# Proiect_TSC_v38.net
KiCad netlist of a schematic drawn in EAGLE
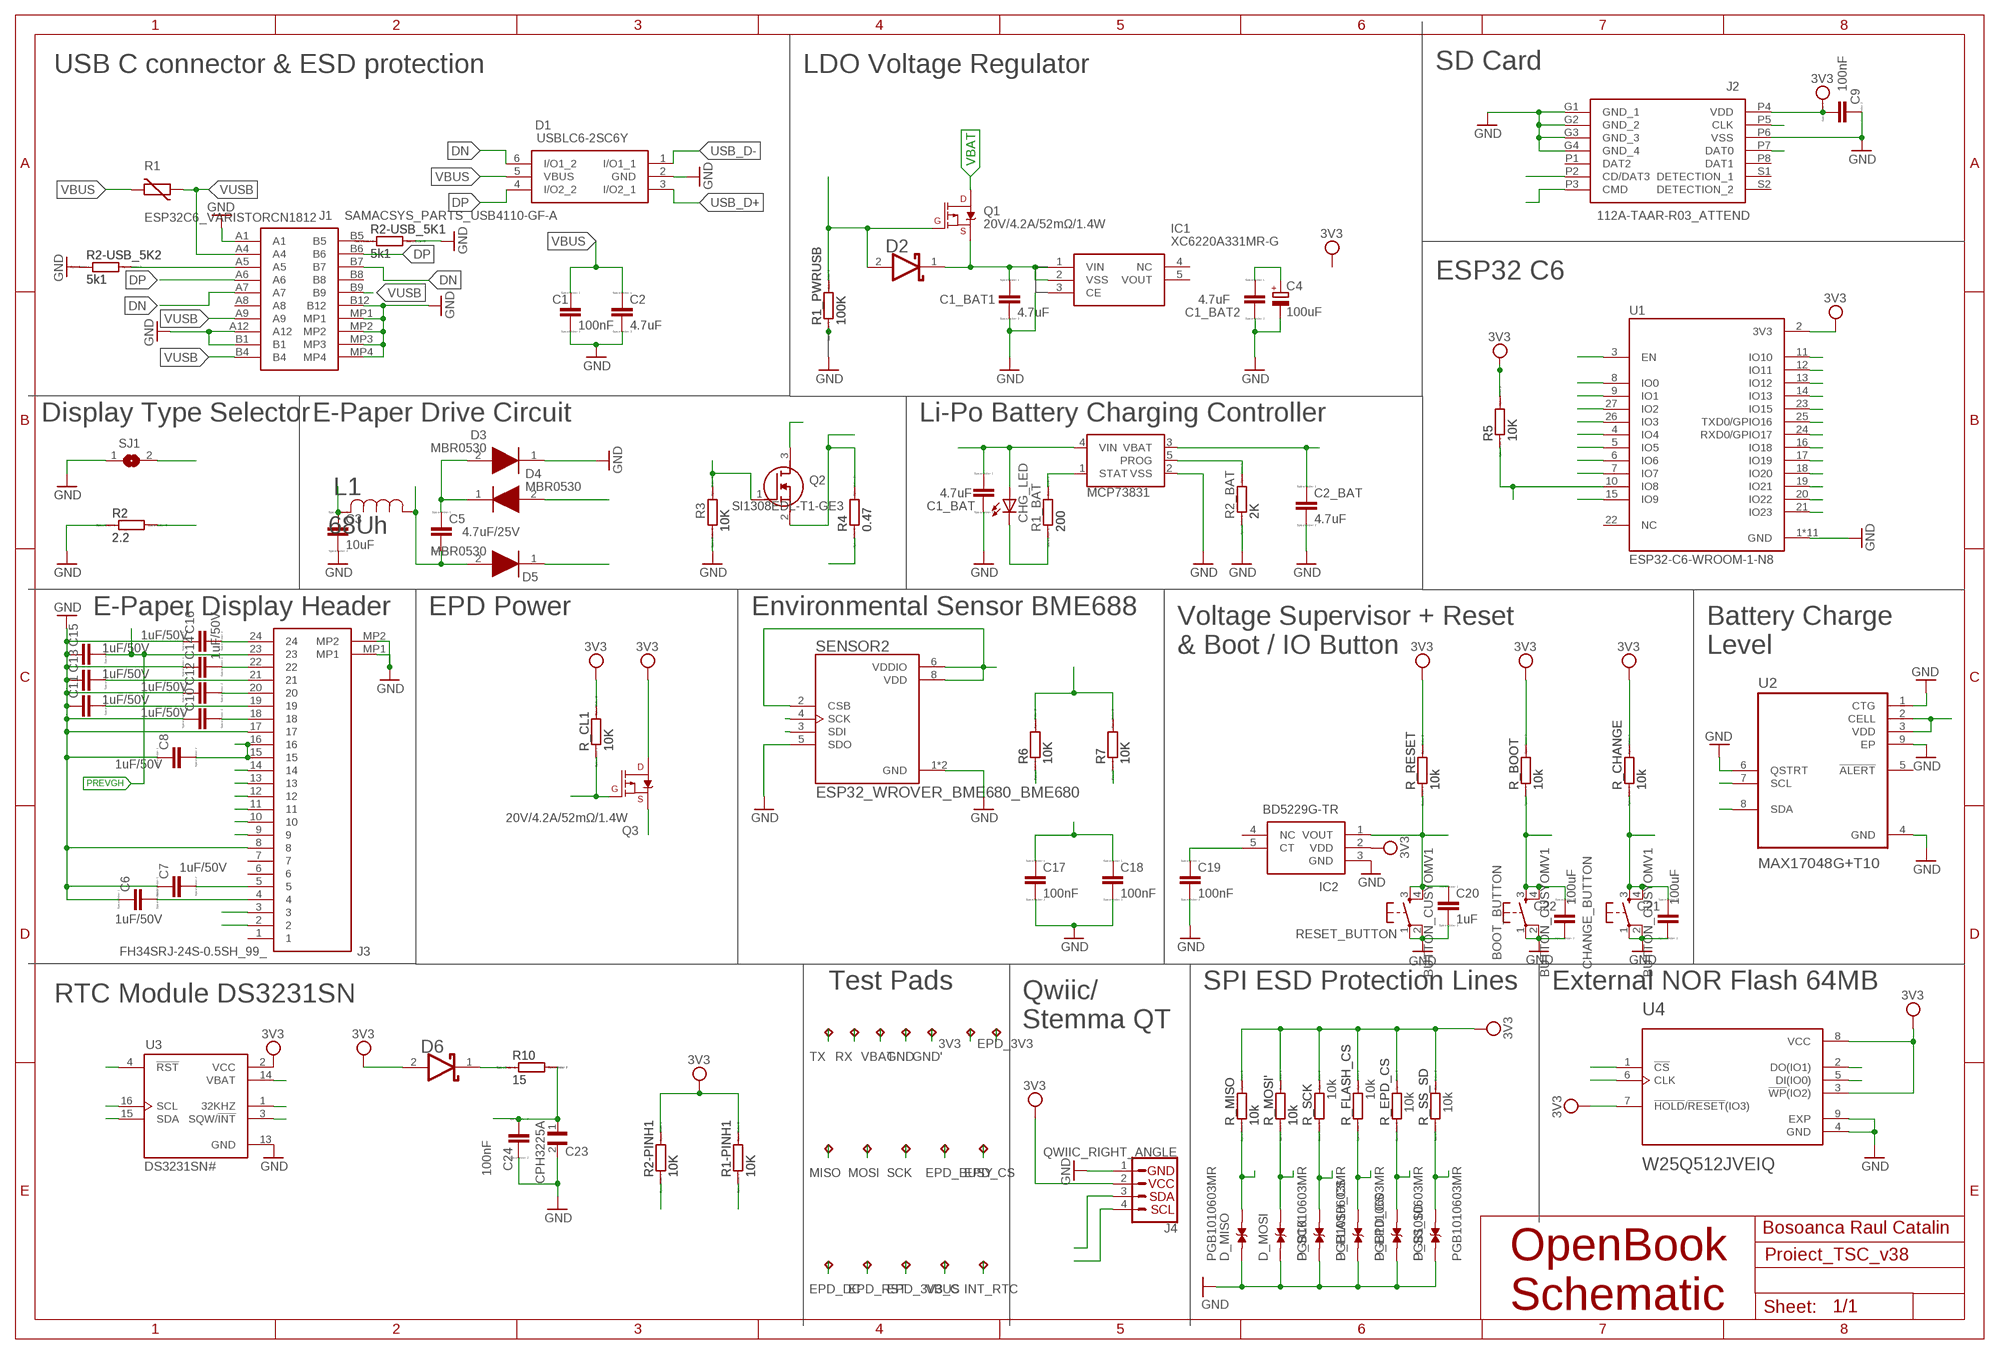
[diagram p0: schematic, sheet 1]

(export (version "E")
  (design (tool "Eeschema 10.0.6"))
  (components
    (comp (ref "3V3")
      (value "TPTP20R")
      (footprint "eagle-import:TP20R")
      (libsource (lib "eagle-import") (part "TPTP20R"))
    )
    (comp (ref "BOOT_BUTTON")
      (value "BUTTON_CUSYOMV1")
      (footprint "eagle-import:MYBUTTON")
      (libsource (lib "eagle-import") (part "BUTTON_CUSYOMV1"))
    )
    (comp (ref "C1")
      (value "100nF")
      (footprint "eagle-import:EAGLE-LTSPICE_C0402")
      (libsource (lib "eagle-import") (part "ESP32_WROVER_EAGLE-LTSPICE_CC0402"))
    )
    (comp (ref "C1_BAT")
      (value "4.7uF")
      (footprint "eagle-import:EAGLE-LTSPICE_C0402")
      (libsource (lib "eagle-import") (part "ESP32_WROVER_EAGLE-LTSPICE_CC0402"))
    )
    (comp (ref "C1_BAT1")
      (value "4.7uF")
      (footprint "eagle-import:EAGLE-LTSPICE_C0402")
      (libsource (lib "eagle-import") (part "ESP32_WROVER_EAGLE-LTSPICE_CC0402"))
    )
    (comp (ref "C1_BAT2")
      (value "4.7uF")
      (footprint "eagle-import:EAGLE-LTSPICE_C0402")
      (libsource (lib "eagle-import") (part "ESP32_WROVER_EAGLE-LTSPICE_CC0402"))
    )
    (comp (ref "C2")
      (value "4.7uF")
      (footprint "eagle-import:EAGLE-LTSPICE_C0402")
      (libsource (lib "eagle-import") (part "ESP32_WROVER_EAGLE-LTSPICE_CC0402"))
    )
    (comp (ref "C2_BAT")
      (value "4.7uF")
      (footprint "eagle-import:EAGLE-LTSPICE_C0402")
      (libsource (lib "eagle-import") (part "ESP32_WROVER_EAGLE-LTSPICE_CC0402"))
    )
    (comp (ref "C3")
      (value "10uF")
      (footprint "eagle-import:EAGLE-LTSPICE_C0402")
      (libsource (lib "eagle-import") (part "ESP32_WROVER_EAGLE-LTSPICE_CC0402"))
    )
    (comp (ref "C4")
      (value "100uF")
      (footprint "eagle-import:RCL_CT3528")
      (libsource (lib "eagle-import") (part "RCL_CPOL-EUCT3528"))
    )
    (comp (ref "C5")
      (value "4.7uF/25V")
      (footprint "eagle-import:EAGLE-LTSPICE_C0402")
      (libsource (lib "eagle-import") (part "ESP32_WROVER_EAGLE-LTSPICE_CC0402"))
    )
    (comp (ref "C6")
      (value "1uF/50V")
      (footprint "eagle-import:EAGLE-LTSPICE_C0402")
      (libsource (lib "eagle-import") (part "EAGLE-LTSPICE_CC0402"))
    )
    (comp (ref "C7")
      (value "1uF/50V")
      (footprint "eagle-import:EAGLE-LTSPICE_C0402")
      (libsource (lib "eagle-import") (part "EAGLE-LTSPICE_CC0402"))
    )
    (comp (ref "C8")
      (value "1uF/50V")
      (footprint "eagle-import:EAGLE-LTSPICE_C0402")
      (libsource (lib "eagle-import") (part "EAGLE-LTSPICE_CC0402"))
    )
    (comp (ref "C9")
      (value "100nF")
      (footprint "eagle-import:EAGLE-LTSPICE_C0402")
      (libsource (lib "eagle-import") (part "ESP32_WROVER_EAGLE-LTSPICE_CC0402"))
    )
    (comp (ref "C10")
      (value "1uF/50V")
      (footprint "eagle-import:EAGLE-LTSPICE_C0402")
      (libsource (lib "eagle-import") (part "EAGLE-LTSPICE_CC0402"))
    )
    (comp (ref "C11")
      (value "1uF/50V")
      (footprint "eagle-import:EAGLE-LTSPICE_C0402")
      (libsource (lib "eagle-import") (part "EAGLE-LTSPICE_CC0402"))
    )
    (comp (ref "C12")
      (value "1uF/50V")
      (footprint "eagle-import:EAGLE-LTSPICE_C0402")
      (libsource (lib "eagle-import") (part "EAGLE-LTSPICE_CC0402"))
    )
    (comp (ref "C13")
      (value "1uF/50V")
      (footprint "eagle-import:EAGLE-LTSPICE_C0402")
      (libsource (lib "eagle-import") (part "EAGLE-LTSPICE_CC0402"))
    )
    (comp (ref "C14")
      (value "1uF/50V")
      (footprint "eagle-import:EAGLE-LTSPICE_C0402")
      (libsource (lib "eagle-import") (part "EAGLE-LTSPICE_CC0402"))
    )
    (comp (ref "C15")
      (value "1uF/50V")
      (footprint "eagle-import:EAGLE-LTSPICE_C0402")
      (libsource (lib "eagle-import") (part "EAGLE-LTSPICE_CC0402"))
    )
    (comp (ref "C16")
      (value "1uF/50V")
      (footprint "eagle-import:EAGLE-LTSPICE_C0402")
      (libsource (lib "eagle-import") (part "EAGLE-LTSPICE_CC0402"))
    )
    (comp (ref "C17")
      (value "100nF")
      (footprint "eagle-import:EAGLE-LTSPICE_C0402")
      (libsource (lib "eagle-import") (part "EAGLE-LTSPICE_CC0402"))
    )
    (comp (ref "C18")
      (value "100nF")
      (footprint "eagle-import:EAGLE-LTSPICE_C0402")
      (libsource (lib "eagle-import") (part "EAGLE-LTSPICE_CC0402"))
    )
    (comp (ref "C19")
      (value "100nF")
      (footprint "eagle-import:EAGLE-LTSPICE_C0402")
      (libsource (lib "eagle-import") (part "EAGLE-LTSPICE_CC0402"))
    )
    (comp (ref "C20")
      (value "1uF")
      (footprint "eagle-import:EAGLE-LTSPICE_C0402")
      (libsource (lib "eagle-import") (part "EAGLE-LTSPICE_CC0402"))
    )
    (comp (ref "C21")
      (value "100uF")
      (footprint "eagle-import:EAGLE-LTSPICE_C0402")
      (libsource (lib "eagle-import") (part "EAGLE-LTSPICE_CC0402"))
    )
    (comp (ref "C22")
      (value "100uF")
      (footprint "eagle-import:EAGLE-LTSPICE_C0402")
      (libsource (lib "eagle-import") (part "EAGLE-LTSPICE_CC0402"))
    )
    (comp (ref "C23")
      (value "100nF")
      (footprint "eagle-import:EAGLE-LTSPICE_C0402")
      (libsource (lib "eagle-import") (part "EAGLE-LTSPICE_CC0402"))
    )
    (comp (ref "C24")
      (value "CPH3225A")
      (footprint "eagle-import:CAPCP3225X100N")
      (fields (field (name "MF") "Seiko Instruments"))
      (libsource (lib "eagle-import") (part "CPH3225A"))
    )
    (comp (ref "CHANGE_BUTTON")
      (value "BUTTON_CUSYOMV1")
      (footprint "eagle-import:MYBUTTON")
      (libsource (lib "eagle-import") (part "BUTTON_CUSYOMV1"))
    )
    (comp (ref "CHG_LED")
      (value "ADAFRUIT_LEDCHIP-LED0603")
      (footprint "eagle-import:ADAFRUIT_CHIP-LED0603")
      (libsource (lib "eagle-import") (part "ADAFRUIT_LEDCHIP-LED0603"))
    )
    (comp (ref "D1")
      (value "USBLC6-2SC6Y")
      (footprint "eagle-import:SOT95P280X145-6N")
      (fields (field (name "MF") "STMicroelectronics"))
      (libsource (lib "eagle-import") (part "USBLC6-2SC6Y"))
    )
    (comp (ref "D2")
      (value "ESP32_WROVER_AVX---SD0805S020S1R0_AVX_SD0805S020S1R0_0_0AVX_SD0805S020S1R0_0_0")
      (footprint "eagle-import:ESP32_WROVER_AVX---SD0805S020S1R0_AVX_SD0805S020S1R0_0")
      (fields
        (field (name "DIGIKEY_PART_NUMBER") "478-7800-1-ND")
        (field (name "MF") "AVX")
        (field (name "MOUSER_PART_NUMBER") "581-SD0805S020S1R0")
      )
      (libsource (lib "eagle-import") (part "ESP32_WROVER_AVX---SD0805S020S1R0_AVX_SD0805S020S1R0_0_0AVX_SD0805S020S1R0_0_0"))
    )
    (comp (ref "D3")
      (value "MBR0530")
      (footprint "eagle-import:SOD3716X135N")
      (fields (field (name "MF") "ON Semiconductor"))
      (libsource (lib "eagle-import") (part "MBR0530"))
    )
    (comp (ref "D4")
      (value "MBR0530")
      (footprint "eagle-import:SOD3716X135N")
      (fields (field (name "MF") "ON Semiconductor"))
      (libsource (lib "eagle-import") (part "MBR0530"))
    )
    (comp (ref "D5")
      (value "MBR0530")
      (footprint "eagle-import:SOD3716X135N")
      (fields (field (name "MF") "ON Semiconductor"))
      (libsource (lib "eagle-import") (part "MBR0530"))
    )
    (comp (ref "D6")
      (value "ESP32_WROVER_AVX---SD0805S020S1R0_AVX_SD0805S020S1R0_0_0AVX_SD0805S020S1R0_0_0")
      (footprint "eagle-import:ESP32_WROVER_AVX---SD0805S020S1R0_AVX_SD0805S020S1R0_0")
      (fields
        (field (name "DIGIKEY_PART_NUMBER") "478-7800-1-ND")
        (field (name "MF") "AVX")
        (field (name "MOUSER_PART_NUMBER") "581-SD0805S020S1R0")
      )
      (libsource (lib "eagle-import") (part "ESP32_WROVER_AVX---SD0805S020S1R0_AVX_SD0805S020S1R0_0_0AVX_SD0805S020S1R0_0_0"))
    )
    (comp (ref "D_EPD_CS")
      (value "PGB1010603MR")
      (footprint "eagle-import:ESP32_WROVER_AVX---SD0805S020S1R0_AVX_SD0805S020S1R0_0")
      (fields (field (name "MF") "Littelfuse Inc."))
      (libsource (lib "eagle-import") (part "PGB1010603MR"))
    )
    (comp (ref "D_FLASH_CS")
      (value "PGB1010603MR")
      (footprint "eagle-import:ESP32_WROVER_AVX---SD0805S020S1R0_AVX_SD0805S020S1R0_0")
      (fields (field (name "MF") "Littelfuse Inc."))
      (libsource (lib "eagle-import") (part "PGB1010603MR"))
    )
    (comp (ref "D_MISO")
      (value "PGB1010603MR")
      (footprint "eagle-import:ESP32_WROVER_AVX---SD0805S020S1R0_AVX_SD0805S020S1R0_0")
      (fields (field (name "MF") "Littelfuse Inc."))
      (libsource (lib "eagle-import") (part "PGB1010603MR"))
    )
    (comp (ref "D_MOSI")
      (value "PGB1010603MR")
      (footprint "eagle-import:ESP32_WROVER_AVX---SD0805S020S1R0_AVX_SD0805S020S1R0_0")
      (fields (field (name "MF") "Littelfuse Inc."))
      (libsource (lib "eagle-import") (part "PGB1010603MR"))
    )
    (comp (ref "D_SCK")
      (value "PGB1010603MR")
      (footprint "eagle-import:ESP32_WROVER_AVX---SD0805S020S1R0_AVX_SD0805S020S1R0_0")
      (fields (field (name "MF") "Littelfuse Inc."))
      (libsource (lib "eagle-import") (part "PGB1010603MR"))
    )
    (comp (ref "D_SS_SD")
      (value "PGB1010603MR")
      (footprint "eagle-import:ESP32_WROVER_AVX---SD0805S020S1R0_AVX_SD0805S020S1R0_0")
      (fields (field (name "MF") "Littelfuse Inc."))
      (libsource (lib "eagle-import") (part "PGB1010603MR"))
    )
    (comp (ref "EPD_3V3")
      (value "TPTP20R")
      (footprint "eagle-import:TP20R")
      (libsource (lib "eagle-import") (part "TPTP20R"))
    )
    (comp (ref "EPD_3V3_C")
      (value "TPTP20R")
      (footprint "eagle-import:TP20R")
      (libsource (lib "eagle-import") (part "TPTP20R"))
    )
    (comp (ref "EPD_BUSY")
      (value "TPTP20R")
      (footprint "eagle-import:TP20R")
      (libsource (lib "eagle-import") (part "TPTP20R"))
    )
    (comp (ref "EPD_CS")
      (value "TPTP20R")
      (footprint "eagle-import:TP20R")
      (libsource (lib "eagle-import") (part "TPTP20R"))
    )
    (comp (ref "EPD_DC")
      (value "TPTP20R")
      (footprint "eagle-import:TP20R")
      (libsource (lib "eagle-import") (part "TPTP20R"))
    )
    (comp (ref "EPD_RST")
      (value "TPTP20R")
      (footprint "eagle-import:TP20R")
      (libsource (lib "eagle-import") (part "TPTP20R"))
    )
    (comp (ref "GND")
      (value "TPTP20R")
      (footprint "eagle-import:TP20R")
      (libsource (lib "eagle-import") (part "TPTP20R"))
    )
    (comp (ref "GND'")
      (value "TPTP20R")
      (footprint "eagle-import:TP20R")
      (libsource (lib "eagle-import") (part "TPTP20R"))
    )
    (comp (ref "IC1")
      (value "XC6220A331MR-G")
      (footprint "eagle-import:SOT95P280X125-5N")
      (fields (field (name "MOUSER_PART_NUMBER") "865-XC6220A331MR-G"))
      (libsource (lib "eagle-import") (part "XC6220A331MR-G"))
    )
    (comp (ref "IC2")
      (value "BD5229G-TR")
      (footprint "eagle-import:SOT95P280X125-5N")
      (fields (field (name "MOUSER_PART_NUMBER") "755-BD5229G-TR"))
      (libsource (lib "eagle-import") (part "BD5229G-TR"))
    )
    (comp (ref "INT_RTC")
      (value "TPTP20R")
      (footprint "eagle-import:TP20R")
      (libsource (lib "eagle-import") (part "TPTP20R"))
    )
    (comp (ref "J1")
      (value "SAMACSYS_PARTS_USB4110-GF-A")
      (footprint "eagle-import:SAMACSYS_PARTS_USB4110GFA")
      (fields
        (field (name "MANUFACTURER_PART_NUMBER") "USB4110-GF-A")
        (field (name "MOUSER_PART_NUMBER") "640-USB4110-GF-A")
      )
      (libsource (lib "eagle-import") (part "SAMACSYS_PARTS_USB4110-GF-A"))
    )
    (comp (ref "J2")
      (value "112A-TAAR-R03_ATTEND")
      (footprint "eagle-import:112ATAARR03ATTEND")
      (fields (field (name "MANUFACTURER_PART_NUMBER") "112A-TAAR-R03 ATTEND"))
      (libsource (lib "eagle-import") (part "112A-TAAR-R03_ATTEND"))
    )
    (comp (ref "J3")
      (value "FH34SRJ-24S-0.5SH_99_")
      (footprint "eagle-import:FH34SRJ24S05SH99")
      (fields
        (field (name "MANUFACTURER_PART_NUMBER") "FH34SRJ-24S-0.5SH(99)")
        (field (name "MOUSER_PART_NUMBER") "798-FH34SRJ24S05SH99")
      )
      (libsource (lib "eagle-import") (part "FH34SRJ-24S-0.5SH_99_"))
    )
    (comp (ref "J4")
      (value "QWIIC_RIGHT_ANGLE")
      (footprint "eagle-import:JST04_1MM_RA")
      (libsource (lib "eagle-import") (part "QWIIC_CONNECTORJS-1MM"))
    )
    (comp (ref "L1")
      (value "68Uh")
      (footprint "eagle-import:IND_4828-WE-TPC_WRE")
      (fields
        (field (name "MANUFACTURER_PART_NUMBER") "744043680")
        (field (name "COPYRIGHT") "Copyright (C) 2024 Ultra Librarian. All rights reserved.")
      )
      (libsource (lib "eagle-import") (part "744043680IND_4828-WE-TPC_WRE"))
    )
    (comp (ref "MCP73831")
      (value "ESP32_WROVER_SPARKFUN-IC-POWER_MCP73831")
      (footprint "eagle-import:ESP32_WROVER_SPARKFUN-IC-POWER_SOT23-5")
      (libsource (lib "eagle-import") (part "ESP32_WROVER_SPARKFUN-IC-POWER_MCP73831"))
    )
    (comp (ref "MISO")
      (value "TPTP20R")
      (footprint "eagle-import:TP20R")
      (libsource (lib "eagle-import") (part "TPTP20R"))
    )
    (comp (ref "MOSI")
      (value "TPTP20R")
      (footprint "eagle-import:TP20R")
      (libsource (lib "eagle-import") (part "TPTP20R"))
    )
    (comp (ref "Q1")
      (value "20V/4.2A/52mΩ/1.4W")
      (footprint "eagle-import:ESP32_WROVER_SPARKFUN-DISCRETESEMI_SOT23-3")
      (libsource (lib "eagle-import") (part "ESP32_WROVER_SPARKFUN-DISCRETESEMI_MOSFET_PCH-DMG2305UX-7"))
    )
    (comp (ref "Q2")
      (value "SI1308EDL-T1-GE3")
      (footprint "eagle-import:SOT65P210X110-3N")
      (fields (field (name "MF") "Vishay Siliconix"))
      (libsource (lib "eagle-import") (part "SI1308EDL-T1-GE3"))
    )
    (comp (ref "Q3")
      (value "20V/4.2A/52mΩ/1.4W")
      (footprint "eagle-import:ESP32_WROVER_SPARKFUN-DISCRETESEMI_SOT23-3")
      (libsource (lib "eagle-import") (part "ESP32_WROVER_SPARKFUN-DISCRETESEMI_MOSFET_PCH-DMG2305UX-7"))
    )
    (comp (ref "R1")
      (value "ESP32C6_VARISTORCN1812")
      (footprint "eagle-import:ESP32C6_VARISTOR_CT_CN1812")
      (libsource (lib "eagle-import") (part "ESP32C6_VARISTORCN1812"))
    )
    (comp (ref "R1-PINH1")
      (value "10K")
      (footprint "eagle-import:EAGLE-LTSPICE_C0402")
      (libsource (lib "eagle-import") (part "ESP32_WROVER_EAGLE-LTSPICE_RR0402"))
    )
    (comp (ref "R1_BAT")
      (value "200")
      (footprint "eagle-import:EAGLE-LTSPICE_C0402")
      (libsource (lib "eagle-import") (part "ESP32_WROVER_EAGLE-LTSPICE_RR0402"))
    )
    (comp (ref "R1_PWRUSB")
      (value "100K")
      (footprint "eagle-import:EAGLE-LTSPICE_C0402")
      (libsource (lib "eagle-import") (part "ESP32_WROVER_EAGLE-LTSPICE_RR0402"))
    )
    (comp (ref "R2")
      (value "2.2")
      (footprint "eagle-import:EAGLE-LTSPICE_C0402")
      (libsource (lib "eagle-import") (part "ESP32_WROVER_EAGLE-LTSPICE_RR0402"))
    )
    (comp (ref "R2-PINH1")
      (value "10K")
      (footprint "eagle-import:EAGLE-LTSPICE_C0402")
      (libsource (lib "eagle-import") (part "ESP32_WROVER_EAGLE-LTSPICE_RR0402"))
    )
    (comp (ref "R2-USB_5K1")
      (value "5k1")
      (footprint "eagle-import:EAGLE-LTSPICE_C0402")
      (libsource (lib "eagle-import") (part "ESP32_WROVER_EAGLE-LTSPICE_RR0402"))
    )
    (comp (ref "R2-USB_5K2")
      (value "5k1")
      (footprint "eagle-import:EAGLE-LTSPICE_C0402")
      (libsource (lib "eagle-import") (part "ESP32_WROVER_EAGLE-LTSPICE_RR0402"))
    )
    (comp (ref "R2_BAT")
      (value "2K")
      (footprint "eagle-import:EAGLE-LTSPICE_C0402")
      (libsource (lib "eagle-import") (part "ESP32_WROVER_EAGLE-LTSPICE_RR0402"))
    )
    (comp (ref "R3")
      (value "10K")
      (footprint "eagle-import:EAGLE-LTSPICE_C0402")
      (libsource (lib "eagle-import") (part "ESP32_WROVER_EAGLE-LTSPICE_RR0402"))
    )
    (comp (ref "R4")
      (value "0.47")
      (footprint "eagle-import:EAGLE-LTSPICE_C0402")
      (libsource (lib "eagle-import") (part "ESP32_WROVER_EAGLE-LTSPICE_RR0402"))
    )
    (comp (ref "R5")
      (value "10K")
      (footprint "eagle-import:EAGLE-LTSPICE_C0402")
      (libsource (lib "eagle-import") (part "ESP32_WROVER_EAGLE-LTSPICE_RR0402"))
    )
    (comp (ref "R6")
      (value "10K")
      (footprint "eagle-import:EAGLE-LTSPICE_C0402")
      (libsource (lib "eagle-import") (part "ESP32_WROVER_EAGLE-LTSPICE_RR0402"))
    )
    (comp (ref "R7")
      (value "10K")
      (footprint "eagle-import:EAGLE-LTSPICE_C0402")
      (libsource (lib "eagle-import") (part "ESP32_WROVER_EAGLE-LTSPICE_RR0402"))
    )
    (comp (ref "R10")
      (value "15")
      (footprint "eagle-import:EAGLE-LTSPICE_C0402")
      (libsource (lib "eagle-import") (part "ESP32_WROVER_EAGLE-LTSPICE_RR0402"))
    )
    (comp (ref "RESET_BUTTON")
      (value "BUTTON_CUSYOMV1")
      (footprint "eagle-import:MYBUTTON")
      (libsource (lib "eagle-import") (part "BUTTON_CUSYOMV1"))
    )
    (comp (ref "RX")
      (value "TPTP20R")
      (footprint "eagle-import:TP20R")
      (libsource (lib "eagle-import") (part "TPTP20R"))
    )
    (comp (ref "R_BOOT")
      (value "10k")
      (footprint "eagle-import:EAGLE-LTSPICE_C0402")
      (libsource (lib "eagle-import") (part "ESP32_WROVER_EAGLE-LTSPICE_RR0402"))
    )
    (comp (ref "R_CHANGE")
      (value "10k")
      (footprint "eagle-import:EAGLE-LTSPICE_C0402")
      (libsource (lib "eagle-import") (part "ESP32_WROVER_EAGLE-LTSPICE_RR0402"))
    )
    (comp (ref "R_CL1")
      (value "10K")
      (footprint "eagle-import:EAGLE-LTSPICE_C0402")
      (libsource (lib "eagle-import") (part "ESP32_WROVER_EAGLE-LTSPICE_RR0402"))
    )
    (comp (ref "R_EPD_CS")
      (value "10k")
      (footprint "eagle-import:EAGLE-LTSPICE_C0402")
      (libsource (lib "eagle-import") (part "ESP32_WROVER_EAGLE-LTSPICE_RR0402"))
    )
    (comp (ref "R_FLASH_CS")
      (value "10k")
      (footprint "eagle-import:EAGLE-LTSPICE_C0402")
      (libsource (lib "eagle-import") (part "ESP32_WROVER_EAGLE-LTSPICE_RR0402"))
    )
    (comp (ref "R_MISO")
      (value "10k")
      (footprint "eagle-import:EAGLE-LTSPICE_C0402")
      (libsource (lib "eagle-import") (part "ESP32_WROVER_EAGLE-LTSPICE_RR0402"))
    )
    (comp (ref "R_MOSI'")
      (value "10k")
      (footprint "eagle-import:EAGLE-LTSPICE_C0402")
      (libsource (lib "eagle-import") (part "ESP32_WROVER_EAGLE-LTSPICE_RR0402"))
    )
    (comp (ref "R_RESET")
      (value "10k")
      (footprint "eagle-import:EAGLE-LTSPICE_C0402")
      (libsource (lib "eagle-import") (part "ESP32_WROVER_EAGLE-LTSPICE_RR0402"))
    )
    (comp (ref "R_SCK")
      (value "10k")
      (footprint "eagle-import:EAGLE-LTSPICE_C0402")
      (libsource (lib "eagle-import") (part "ESP32_WROVER_EAGLE-LTSPICE_RR0402"))
    )
    (comp (ref "R_SS_SD")
      (value "10k")
      (footprint "eagle-import:EAGLE-LTSPICE_C0402")
      (libsource (lib "eagle-import") (part "ESP32_WROVER_EAGLE-LTSPICE_RR0402"))
    )
    (comp (ref "SCK")
      (value "TPTP20R")
      (footprint "eagle-import:TP20R")
      (libsource (lib "eagle-import") (part "TPTP20R"))
    )
    (comp (ref "SENSOR2")
      (value "ESP32_WROVER_BME680_BME680")
      (footprint "eagle-import:ESP32_WROVER_BME680_PSON80P300X300X100-8N")
      (fields (field (name "MF") "Bosch Sensortec") (field (name "MP") "BME680"))
      (libsource (lib "eagle-import") (part "ESP32_WROVER_BME680_BME680"))
    )
    (comp (ref "SJ1") (value "SJ") (footprint "eagle-import:SJ") (libsource (lib "eagle-import") (part "SJ")))
    (comp (ref "TX")
      (value "TPTP20R")
      (footprint "eagle-import:TP20R")
      (libsource (lib "eagle-import") (part "TPTP20R"))
    )
    (comp (ref "U1")
      (value "ESP32-C6-WROOM-1-N8")
      (footprint "eagle-import:XCVR_ESP32-C6-WROOM-1-N8")
      (fields (field (name "MF") "Espressif Systems"))
      (libsource (lib "eagle-import") (part "ESP32-C6-WROOM-1-N8"))
    )
    (comp (ref "U2")
      (value "MAX17048G+T10")
      (footprint "eagle-import:SON50P200X200X80-9N")
      (fields (field (name "MF") "Analog Devices"))
      (libsource (lib "eagle-import") (part "MAX17048G+T10"))
    )
    (comp (ref "U3")
      (value "DS3231SN#")
      (footprint "eagle-import:SOIC127P1032X265-16N")
      (fields (field (name "MF") "Analog Devices"))
      (libsource (lib "eagle-import") (part "DS3231SN#"))
    )
    (comp (ref "U4")
      (value "W25Q512JVEIQ")
      (footprint "eagle-import:SON127P600X800X80-9N")
      (fields (field (name "MF") "Winbond Electronics"))
      (libsource (lib "eagle-import") (part "W25Q512JVEIQ"))
    )
    (comp (ref "VBAT")
      (value "TPTP20R")
      (footprint "eagle-import:TP20R")
      (libsource (lib "eagle-import") (part "TPTP20R"))
    )
    (comp (ref "VBUS")
      (value "TPTP20R")
      (footprint "eagle-import:TP20R")
      (libsource (lib "eagle-import") (part "TPTP20R"))
    )
  )
  (nets
    (net (code "1") (name "3V3") (class "Default")
      (node (ref "3V3") (pin "TP") (pinfunction "TP_TP") (pintype "input"))
      (node (ref "C9") (pin "1") (pinfunction "1_1") (pintype "passive"))
      (node (ref "D6") (pin "2") (pinfunction "ANODE_2") (pintype "bidirectional"))
      (node (ref "IC2") (pin "2") (pinfunction "VDD_2") (pintype "bidirectional"))
      (node (ref "J2") (pin "P4") (pinfunction "VDD_P4") (pintype "bidirectional"))
      (node (ref "J4") (pin "2") (pinfunction "2_2") (pintype "power_in"))
      (node (ref "Q3") (pin "3") (pinfunction "D_3") (pintype "bidirectional"))
      (node (ref "R1-PINH1") (pin "2") (pinfunction "2_2") (pintype "passive"))
      (node (ref "R2-PINH1") (pin "2") (pinfunction "2_2") (pintype "passive"))
      (node (ref "R5") (pin "2") (pinfunction "2_2") (pintype "passive"))
      (node (ref "R_BOOT") (pin "2") (pinfunction "2_2") (pintype "passive"))
      (node (ref "R_CHANGE") (pin "2") (pinfunction "2_2") (pintype "passive"))
      (node (ref "R_CL1") (pin "2") (pinfunction "2_2") (pintype "passive"))
      (node (ref "R_EPD_CS") (pin "2") (pinfunction "2_2") (pintype "passive"))
      (node (ref "R_FLASH_CS") (pin "2") (pinfunction "2_2") (pintype "passive"))
      (node (ref "R_MISO") (pin "2") (pinfunction "2_2") (pintype "passive"))
      (node (ref "R_MOSI'") (pin "2") (pinfunction "2_2") (pintype "passive"))
      (node (ref "R_RESET") (pin "2") (pinfunction "2_2") (pintype "passive"))
      (node (ref "R_SCK") (pin "2") (pinfunction "2_2") (pintype "passive"))
      (node (ref "R_SS_SD") (pin "2") (pinfunction "2_2") (pintype "passive"))
      (node (ref "U1") (pin "2") (pinfunction "3V3_2") (pintype "power_in"))
      (node (ref "U3") (pin "2") (pinfunction "VCC_2") (pintype "power_in"))
      (node (ref "U4") (pin "3") (pinfunction "~{WP}(IO2)_3") (pintype "bidirectional"))
      (node (ref "U4") (pin "7") (pinfunction "~{HOLD}/~{RESET}(IO3)_7") (pintype "bidirectional"))
      (node (ref "U4") (pin "8") (pinfunction "VCC_8") (pintype "power_in"))
    )
    (net (code "2") (name "32KHZ") (class "Default")
      (node (ref "R2-PINH1") (pin "1") (pinfunction "1_1") (pintype "passive"))
      (node (ref "U1") (pin "9") (pinfunction "IO1_9") (pintype "bidirectional"))
      (node (ref "U3") (pin "1") (pinfunction "32KHZ_1") (pintype "output"))
    )
    (net (code "3") (name "DN") (class "Default")
      (node (ref "D1") (pin "6") (pinfunction "I/O1_2_6") (pintype "bidirectional"))
      (node (ref "J1") (pin "A7") (pinfunction "A7_A7") (pintype "bidirectional"))
      (node (ref "J1") (pin "B7") (pinfunction "B7_B7") (pintype "bidirectional"))
    )
    (net (code "4") (name "DP") (class "Default")
      (node (ref "D1") (pin "4") (pinfunction "I/O2_2_4") (pintype "bidirectional"))
      (node (ref "J1") (pin "A6") (pinfunction "A6_A6") (pintype "bidirectional"))
      (node (ref "J1") (pin "B6") (pinfunction "B6_B6") (pintype "bidirectional"))
    )
    (net (code "5") (name "EPD_3V3") (class "Default")
      (node (ref "C3") (pin "1") (pinfunction "1_1") (pintype "passive"))
      (node (ref "C8") (pin "2") (pinfunction "2_2") (pintype "passive"))
      (node (ref "EPD_3V3") (pin "TP") (pinfunction "TP_TP") (pintype "input"))
      (node (ref "J3") (pin "15") (pinfunction "15_15") (pintype "bidirectional"))
      (node (ref "J3") (pin "16") (pinfunction "16_16") (pintype "bidirectional"))
      (node (ref "L1") (pin "2") (pinfunction "2_2") (pintype "passive"))
      (node (ref "Q3") (pin "2") (pinfunction "S_2") (pintype "bidirectional"))
    )
    (net (code "6") (name "EPD_3V3_C") (class "Default")
      (node (ref "EPD_3V3_C") (pin "TP") (pinfunction "TP_TP") (pintype "input"))
      (node (ref "Q3") (pin "1") (pinfunction "G_1") (pintype "bidirectional"))
      (node (ref "R_CL1") (pin "1") (pinfunction "1_1") (pintype "passive"))
      (node (ref "U1") (pin "18") (pinfunction "IO20_18") (pintype "bidirectional"))
    )
    (net (code "7") (name "EPD_BUSY") (class "Default")
      (node (ref "EPD_BUSY") (pin "TP") (pinfunction "TP_TP") (pintype "input"))
      (node (ref "J3") (pin "9") (pinfunction "9_9") (pintype "bidirectional"))
      (node (ref "U1") (pin "26") (pinfunction "IO3_26") (pintype "bidirectional"))
    )
    (net (code "8") (name "EPD_CS") (class "Default")
      (node (ref "D_EPD_CS") (pin "2") (pinfunction "2_2") (pintype "passive"))
      (node (ref "EPD_CS") (pin "TP") (pinfunction "TP_TP") (pintype "input"))
      (node (ref "J3") (pin "12") (pinfunction "12_12") (pintype "bidirectional"))
      (node (ref "R_EPD_CS") (pin "1") (pinfunction "1_1") (pintype "passive"))
      (node (ref "U1") (pin "11") (pinfunction "IO10_11") (pintype "bidirectional"))
    )
    (net (code "9") (name "EPD_DC") (class "Default")
      (node (ref "EPD_DC") (pin "TP") (pinfunction "TP_TP") (pintype "input"))
      (node (ref "J3") (pin "11") (pinfunction "11_11") (pintype "bidirectional"))
      (node (ref "U1") (pin "5") (pinfunction "IO5_5") (pintype "bidirectional"))
    )
    (net (code "10") (name "EPD_RST") (class "Default")
      (node (ref "EPD_RST") (pin "TP") (pinfunction "TP_TP") (pintype "input"))
      (node (ref "J3") (pin "10") (pinfunction "10_10") (pintype "bidirectional"))
      (node (ref "U1") (pin "21") (pinfunction "IO23_21") (pintype "bidirectional"))
    )
    (net (code "11") (name "FLASH_CS") (class "Default")
      (node (ref "D_FLASH_CS") (pin "2") (pinfunction "2_2") (pintype "passive"))
      (node (ref "R_FLASH_CS") (pin "1") (pinfunction "1_1") (pintype "passive"))
      (node (ref "U1") (pin "12") (pinfunction "IO11_12") (pintype "bidirectional"))
      (node (ref "U4") (pin "1") (pinfunction "~{CS}_1") (pintype "input"))
    )
    (net (code "12") (name "GDR") (class "Default")
      (node (ref "J3") (pin "2") (pinfunction "2_2") (pintype "bidirectional"))
      (node (ref "Q2") (pin "1") (pinfunction "G_1") (pintype "bidirectional"))
      (node (ref "R3") (pin "2") (pinfunction "2_2") (pintype "passive"))
    )
    (net (code "13") (name "GND") (class "Default")
      (node (ref "BOOT_BUTTON") (pin "1") (pinfunction "1_1") (pintype "passive"))
      (node (ref "BOOT_BUTTON") (pin "2") (pinfunction "2_2") (pintype "passive"))
      (node (ref "C1") (pin "2") (pinfunction "2_2") (pintype "passive"))
      (node (ref "C10") (pin "1") (pinfunction "1_1") (pintype "passive"))
      (node (ref "C11") (pin "1") (pinfunction "1_1") (pintype "passive"))
      (node (ref "C12") (pin "1") (pinfunction "1_1") (pintype "passive"))
      (node (ref "C13") (pin "1") (pinfunction "1_1") (pintype "passive"))
      (node (ref "C14") (pin "1") (pinfunction "1_1") (pintype "passive"))
      (node (ref "C15") (pin "1") (pinfunction "1_1") (pintype "passive"))
      (node (ref "C16") (pin "1") (pinfunction "1_1") (pintype "passive"))
      (node (ref "C17") (pin "2") (pinfunction "2_2") (pintype "passive"))
      (node (ref "C18") (pin "2") (pinfunction "2_2") (pintype "passive"))
      (node (ref "C19") (pin "2") (pinfunction "2_2") (pintype "passive"))
      (node (ref "C1_BAT") (pin "2") (pinfunction "2_2") (pintype "passive"))
      (node (ref "C1_BAT1") (pin "2") (pinfunction "2_2") (pintype "passive"))
      (node (ref "C1_BAT2") (pin "2") (pinfunction "2_2") (pintype "passive"))
      (node (ref "C2") (pin "2") (pinfunction "2_2") (pintype "passive"))
      (node (ref "C20") (pin "2") (pinfunction "2_2") (pintype "passive"))
      (node (ref "C21") (pin "2") (pinfunction "2_2") (pintype "passive"))
      (node (ref "C22") (pin "2") (pinfunction "2_2") (pintype "passive"))
      (node (ref "C23") (pin "2") (pinfunction "2_2") (pintype "passive"))
      (node (ref "C24") (pin "2") (pinfunction "2_2") (pintype "passive"))
      (node (ref "C2_BAT") (pin "2") (pinfunction "2_2") (pintype "passive"))
      (node (ref "C3") (pin "2") (pinfunction "2_2") (pintype "passive"))
      (node (ref "C4") (pin "-") (pinfunction "-_-") (pintype "passive"))
      (node (ref "C6") (pin "1") (pinfunction "1_1") (pintype "passive"))
      (node (ref "C7") (pin "1") (pinfunction "1_1") (pintype "passive"))
      (node (ref "C8") (pin "1") (pinfunction "1_1") (pintype "passive"))
      (node (ref "C9") (pin "2") (pinfunction "2_2") (pintype "passive"))
      (node (ref "CHANGE_BUTTON") (pin "1") (pinfunction "1_1") (pintype "passive"))
      (node (ref "CHANGE_BUTTON") (pin "2") (pinfunction "2_2") (pintype "passive"))
      (node (ref "D1") (pin "2") (pinfunction "GND_2") (pintype "bidirectional"))
      (node (ref "D3") (pin "1") (pinfunction "K_1") (pintype "bidirectional"))
      (node (ref "D_EPD_CS") (pin "1") (pinfunction "1_1") (pintype "passive"))
      (node (ref "D_FLASH_CS") (pin "1") (pinfunction "1_1") (pintype "passive"))
      (node (ref "D_MISO") (pin "1") (pinfunction "1_1") (pintype "passive"))
      (node (ref "D_MOSI") (pin "1") (pinfunction "1_1") (pintype "passive"))
      (node (ref "D_SCK") (pin "1") (pinfunction "1_1") (pintype "passive"))
      (node (ref "D_SS_SD") (pin "1") (pinfunction "1_1") (pintype "passive"))
      (node (ref "GND") (pin "TP") (pinfunction "TP_TP") (pintype "input"))
      (node (ref "GND'") (pin "TP") (pinfunction "TP_TP") (pintype "input"))
      (node (ref "IC2") (pin "3") (pinfunction "GND_3") (pintype "bidirectional"))
      (node (ref "J1") (pin "A1") (pinfunction "A1_A1") (pintype "bidirectional"))
      (node (ref "J1") (pin "A12") (pinfunction "A12_A12") (pintype "bidirectional"))
      (node (ref "J1") (pin "B1") (pinfunction "B1_B1") (pintype "bidirectional"))
      (node (ref "J1") (pin "B12") (pinfunction "B12_B12") (pintype "bidirectional"))
      (node (ref "J1") (pin "MP1") (pinfunction "MP1_MP1") (pintype "bidirectional"))
      (node (ref "J1") (pin "MP2") (pinfunction "MP2_MP2") (pintype "bidirectional"))
      (node (ref "J1") (pin "MP3") (pinfunction "MP3_MP3") (pintype "bidirectional"))
      (node (ref "J1") (pin "MP4") (pinfunction "MP4_MP4") (pintype "bidirectional"))
      (node (ref "J2") (pin "G1") (pinfunction "GND_1_G1") (pintype "bidirectional"))
      (node (ref "J2") (pin "G2") (pinfunction "GND_2_G2") (pintype "bidirectional"))
      (node (ref "J2") (pin "G3") (pinfunction "GND_3_G3") (pintype "bidirectional"))
      (node (ref "J2") (pin "G4") (pinfunction "GND_4_G4") (pintype "bidirectional"))
      (node (ref "J2") (pin "P6") (pinfunction "VSS_P6") (pintype "bidirectional"))
      (node (ref "J3") (pin "17") (pinfunction "17_17") (pintype "bidirectional"))
      (node (ref "J3") (pin "8") (pinfunction "8_8") (pintype "bidirectional"))
      (node (ref "J3") (pin "MP1") (pinfunction "MP1_MP1") (pintype "bidirectional"))
      (node (ref "J3") (pin "MP2") (pinfunction "MP2_MP2") (pintype "bidirectional"))
      (node (ref "J4") (pin "1") (pinfunction "1_1") (pintype "power_in"))
      (node (ref "MCP73831") (pin "2") (pinfunction "VSS_2") (pintype "power_in"))
      (node (ref "R1_PWRUSB") (pin "1") (pinfunction "1_1") (pintype "passive"))
      (node (ref "R2") (pin "1") (pinfunction "1_1") (pintype "passive"))
      (node (ref "R2-USB_5K1") (pin "2") (pinfunction "2_2") (pintype "passive"))
      (node (ref "R2-USB_5K2") (pin "1") (pinfunction "1_1") (pintype "passive"))
      (node (ref "R2_BAT") (pin "1") (pinfunction "1_1") (pintype "passive"))
      (node (ref "R3") (pin "1") (pinfunction "1_1") (pintype "passive"))
      (node (ref "RESET_BUTTON") (pin "1") (pinfunction "1_1") (pintype "passive"))
      (node (ref "RESET_BUTTON") (pin "2") (pinfunction "2_2") (pintype "passive"))
      (node (ref "SENSOR2") (pin "1") (pinfunction "GND_1") (pintype "power_in"))
      (node (ref "SENSOR2") (pin "5") (pinfunction "SDO_5") (pintype "bidirectional"))
      (node (ref "SENSOR2") (pin "7") (pinfunction "GND_7") (pintype "power_in"))
      (node (ref "SJ1") (pin "1") (pinfunction "1_1") (pintype "passive"))
      (node (ref "U1") (pin "1") (pinfunction "GND_1") (pintype "power_in"))
      (node (ref "U1") (pin "28") (pinfunction "GND_28") (pintype "power_in"))
      (node (ref "U1") (pin "29_1") (pinfunction "GND_29_1") (pintype "power_in"))
      (node (ref "U1") (pin "29_2") (pinfunction "GND_29_2") (pintype "power_in"))
      (node (ref "U1") (pin "29_3") (pinfunction "GND_29_3") (pintype "power_in"))
      (node (ref "U1") (pin "29_4") (pinfunction "GND_29_4") (pintype "power_in"))
      (node (ref "U1") (pin "29_5") (pinfunction "GND_29_5") (pintype "power_in"))
      (node (ref "U1") (pin "29_6") (pinfunction "GND_29_6") (pintype "power_in"))
      (node (ref "U1") (pin "29_7") (pinfunction "GND_29_7") (pintype "power_in"))
      (node (ref "U1") (pin "29_8") (pinfunction "GND_29_8") (pintype "power_in"))
      (node (ref "U1") (pin "29_9") (pinfunction "GND_29_9") (pintype "power_in"))
      (node (ref "U2") (pin "1") (pinfunction "CTG_1") (pintype "power_in"))
      (node (ref "U2") (pin "4") (pinfunction "GND_4") (pintype "power_in"))
      (node (ref "U2") (pin "6") (pinfunction "QSTRT_6") (pintype "input"))
      (node (ref "U2") (pin "9") (pinfunction "EP_9") (pintype "power_in"))
      (node (ref "U3") (pin "13") (pinfunction "GND_13") (pintype "power_in"))
      (node (ref "U4") (pin "4") (pinfunction "GND_4") (pintype "power_in"))
      (node (ref "U4") (pin "9") (pinfunction "EXP_9") (pintype "passive"))
    )
    (net (code "14") (name "GPIO8") (class "Default")
      (node (ref "R5") (pin "1") (pinfunction "1_1") (pintype "passive"))
      (node (ref "U1") (pin "10") (pinfunction "IO8_10") (pintype "bidirectional"))
    )
    (net (code "15") (name "I2C_PW") (class "Default")
      (node (ref "C17") (pin "1") (pinfunction "1_1") (pintype "passive"))
      (node (ref "C18") (pin "1") (pinfunction "1_1") (pintype "passive"))
      (node (ref "R6") (pin "2") (pinfunction "2_2") (pintype "passive"))
      (node (ref "R7") (pin "2") (pinfunction "2_2") (pintype "passive"))
      (node (ref "SENSOR2") (pin "2") (pinfunction "CSB_2") (pintype "input"))
      (node (ref "SENSOR2") (pin "6") (pinfunction "VDDIO_6") (pintype "power_in"))
      (node (ref "SENSOR2") (pin "8") (pinfunction "VDD_8") (pintype "power_in"))
      (node (ref "U1") (pin "17") (pinfunction "IO19_17") (pintype "bidirectional"))
    )
    (net (code "16") (name "INT_RTC") (class "Default")
      (node (ref "INT_RTC") (pin "TP") (pinfunction "TP_TP") (pintype "input"))
      (node (ref "R1-PINH1") (pin "1") (pinfunction "1_1") (pintype "passive"))
      (node (ref "U1") (pin "8") (pinfunction "IO0_8") (pintype "bidirectional"))
      (node (ref "U3") (pin "3") (pinfunction "SQW/~{INT}_3") (pintype "output"))
    )
    (net (code "17") (name "IO{slash}BOOT") (class "Default")
      (node (ref "BOOT_BUTTON") (pin "3") (pinfunction "3_3") (pintype "passive"))
      (node (ref "BOOT_BUTTON") (pin "4") (pinfunction "4_4") (pintype "passive"))
      (node (ref "C22") (pin "1") (pinfunction "1_1") (pintype "passive"))
      (node (ref "R_BOOT") (pin "1") (pinfunction "1_1") (pintype "passive"))
      (node (ref "U1") (pin "15") (pinfunction "IO9_15") (pintype "bidirectional"))
    )
    (net (code "18") (name "IO{slash}CHANGE") (class "Default")
      (node (ref "C21") (pin "1") (pinfunction "1_1") (pintype "passive"))
      (node (ref "CHANGE_BUTTON") (pin "3") (pinfunction "3_3") (pintype "passive"))
      (node (ref "CHANGE_BUTTON") (pin "4") (pinfunction "4_4") (pintype "passive"))
      (node (ref "R_CHANGE") (pin "1") (pinfunction "1_1") (pintype "passive"))
      (node (ref "U1") (pin "23") (pinfunction "IO15_23") (pintype "bidirectional"))
    )
    (net (code "19") (name "MISO") (class "Default")
      (node (ref "D_MISO") (pin "2") (pinfunction "2_2") (pintype "passive"))
      (node (ref "J2") (pin "P7") (pinfunction "DAT0_P7") (pintype "bidirectional"))
      (node (ref "MISO") (pin "TP") (pinfunction "TP_TP") (pintype "input"))
      (node (ref "R_MISO") (pin "1") (pinfunction "1_1") (pintype "passive"))
      (node (ref "U1") (pin "27") (pinfunction "IO2_27") (pintype "bidirectional"))
      (node (ref "U4") (pin "2") (pinfunction "DO(IO1)_2") (pintype "bidirectional"))
    )
    (net (code "20") (name "MOSI") (class "Default")
      (node (ref "D_MOSI") (pin "2") (pinfunction "2_2") (pintype "passive"))
      (node (ref "J2") (pin "P3") (pinfunction "CMD_P3") (pintype "bidirectional"))
      (node (ref "J3") (pin "14") (pinfunction "14_14") (pintype "bidirectional"))
      (node (ref "MOSI") (pin "TP") (pinfunction "TP_TP") (pintype "input"))
      (node (ref "R_MOSI'") (pin "1") (pinfunction "1_1") (pintype "passive"))
      (node (ref "U1") (pin "7") (pinfunction "IO7_7") (pintype "bidirectional"))
      (node (ref "U4") (pin "5") (pinfunction "DI(IO0)_5") (pintype "bidirectional"))
    )
    (net (code "21") (name "Net-(C1_BAT2-Pad1)") (class "Default")
      (node (ref "C1_BAT2") (pin "1") (pinfunction "1_1") (pintype "passive"))
      (node (ref "C4") (pin "+") (pinfunction "+_+") (pintype "passive"))
    )
    (net (code "22") (name "Net-(C6-Pad2)") (class "Default")
      (node (ref "C6") (pin "2") (pinfunction "2_2") (pintype "passive"))
      (node (ref "J3") (pin "4") (pinfunction "4_4") (pintype "bidirectional"))
    )
    (net (code "23") (name "Net-(C7-Pad2)") (class "Default")
      (node (ref "C7") (pin "2") (pinfunction "2_2") (pintype "passive"))
      (node (ref "J3") (pin "5") (pinfunction "5_5") (pintype "bidirectional"))
    )
    (net (code "24") (name "Net-(C10-Pad2)") (class "Default")
      (node (ref "C10") (pin "2") (pinfunction "2_2") (pintype "passive"))
      (node (ref "J3") (pin "18") (pinfunction "18_18") (pintype "bidirectional"))
    )
    (net (code "25") (name "Net-(C11-Pad2)") (class "Default")
      (node (ref "C11") (pin "2") (pinfunction "2_2") (pintype "passive"))
      (node (ref "J3") (pin "19") (pinfunction "19_19") (pintype "bidirectional"))
    )
    (net (code "26") (name "Net-(C12-Pad2)") (class "Default")
      (node (ref "C12") (pin "2") (pinfunction "2_2") (pintype "passive"))
      (node (ref "J3") (pin "20") (pinfunction "20_20") (pintype "bidirectional"))
    )
    (net (code "27") (name "Net-(C14-Pad2)") (class "Default")
      (node (ref "C14") (pin "2") (pinfunction "2_2") (pintype "passive"))
      (node (ref "J3") (pin "22") (pinfunction "22_22") (pintype "bidirectional"))
    )
    (net (code "28") (name "Net-(C16-Pad2)") (class "Default")
      (node (ref "C16") (pin "2") (pinfunction "2_2") (pintype "passive"))
      (node (ref "J3") (pin "24") (pinfunction "24_24") (pintype "bidirectional"))
    )
    (net (code "29") (name "Net-(CHG_LED-PadC)") (class "Default")
      (node (ref "CHG_LED") (pin "C") (pinfunction "C_C") (pintype "passive"))
      (node (ref "R1_BAT") (pin "1") (pinfunction "1_1") (pintype "passive"))
    )
    (net (code "30") (name "Net-(D2-CATHODE)") (class "Default")
      (node (ref "C1_BAT1") (pin "1") (pinfunction "1_1") (pintype "passive"))
      (node (ref "D2") (pin "1") (pinfunction "CATHODE_1") (pintype "bidirectional"))
      (node (ref "IC1") (pin "1") (pinfunction "VIN_1") (pintype "bidirectional"))
      (node (ref "IC1") (pin "2") (pinfunction "VSS_2") (pintype "bidirectional"))
      (node (ref "Q1") (pin "2") (pinfunction "S_2") (pintype "bidirectional"))
    )
    (net (code "31") (name "Net-(D3-A)") (class "Default")
      (node (ref "C5") (pin "1") (pinfunction "1_1") (pintype "passive"))
      (node (ref "D3") (pin "2") (pinfunction "A_2") (pintype "bidirectional"))
      (node (ref "D4") (pin "1") (pinfunction "K_1") (pintype "bidirectional"))
    )
    (net (code "32") (name "Net-(D6-CATHODE)") (class "Default")
      (node (ref "D6") (pin "1") (pinfunction "CATHODE_1") (pintype "bidirectional"))
      (node (ref "R10") (pin "1") (pinfunction "1_1") (pintype "passive"))
    )
    (net (code "33") (name "Net-(IC2-CT)") (class "Default")
      (node (ref "C19") (pin "1") (pinfunction "1_1") (pintype "passive"))
      (node (ref "IC2") (pin "5") (pinfunction "CT_5") (pintype "bidirectional"))
    )
    (net (code "34") (name "Net-(J1-PadA5)") (class "Default")
      (node (ref "J1") (pin "A5") (pinfunction "A5_A5") (pintype "bidirectional"))
      (node (ref "R2-USB_5K2") (pin "2") (pinfunction "2_2") (pintype "passive"))
    )
    (net (code "35") (name "Net-(J1-PadB5)") (class "Default")
      (node (ref "J1") (pin "B5") (pinfunction "B5_B5") (pintype "bidirectional"))
      (node (ref "R2-USB_5K1") (pin "1") (pinfunction "1_1") (pintype "passive"))
    )
    (net (code "36") (name "Net-(MCP73831-PROG)") (class "Default")
      (node (ref "MCP73831") (pin "5") (pinfunction "PROG_5") (pintype "input"))
      (node (ref "R2_BAT") (pin "2") (pinfunction "2_2") (pintype "passive"))
    )
    (net (code "37") (name "Net-(MCP73831-STAT)") (class "Default")
      (node (ref "MCP73831") (pin "1") (pinfunction "STAT_1") (pintype "output"))
      (node (ref "R1_BAT") (pin "2") (pinfunction "2_2") (pintype "passive"))
    )
    (net (code "38") (name "PREVGH") (class "Default")
      (node (ref "C13") (pin "2") (pinfunction "2_2") (pintype "passive"))
      (node (ref "D5") (pin "1") (pinfunction "K_1") (pintype "bidirectional"))
      (node (ref "J3") (pin "21") (pinfunction "21_21") (pintype "bidirectional"))
    )
    (net (code "39") (name "PREVGL") (class "Default")
      (node (ref "C15") (pin "2") (pinfunction "2_2") (pintype "passive"))
      (node (ref "D4") (pin "2") (pinfunction "A_2") (pintype "bidirectional"))
      (node (ref "J3") (pin "23") (pinfunction "23_23") (pintype "bidirectional"))
    )
    (net (code "40") (name "RESE") (class "Default")
      (node (ref "J3") (pin "3") (pinfunction "3_3") (pintype "bidirectional"))
      (node (ref "Q2") (pin "2") (pinfunction "S_2") (pintype "bidirectional"))
      (node (ref "R4") (pin "2") (pinfunction "2_2") (pintype "passive"))
    )
    (net (code "41") (name "RESE'") (class "Default")
      (node (ref "R2") (pin "2") (pinfunction "2_2") (pintype "passive"))
      (node (ref "R4") (pin "1") (pinfunction "1_1") (pintype "passive"))
      (node (ref "SJ1") (pin "2") (pinfunction "2_2") (pintype "passive"))
    )
    (net (code "42") (name "RESET") (class "Default")
      (node (ref "C20") (pin "1") (pinfunction "1_1") (pintype "passive"))
      (node (ref "IC2") (pin "1") (pinfunction "VOUT_1") (pintype "bidirectional"))
      (node (ref "RESET_BUTTON") (pin "3") (pinfunction "3_3") (pintype "passive"))
      (node (ref "RESET_BUTTON") (pin "4") (pinfunction "4_4") (pintype "passive"))
      (node (ref "R_RESET") (pin "1") (pinfunction "1_1") (pintype "passive"))
      (node (ref "U1") (pin "3") (pinfunction "EN_3") (pintype "input"))
    )
    (net (code "43") (name "RTC_RST") (class "Default")
      (node (ref "U1") (pin "16") (pinfunction "IO18_16") (pintype "bidirectional"))
      (node (ref "U3") (pin "4") (pinfunction "~{RST}_4") (pintype "input"))
    )
    (net (code "44") (name "RX") (class "Default")
      (node (ref "RX") (pin "TP") (pinfunction "TP_TP") (pintype "input"))
      (node (ref "U1") (pin "24") (pinfunction "RXD0/GPIO17_24") (pintype "bidirectional"))
    )
    (net (code "45") (name "SCK") (class "Default")
      (node (ref "D_SCK") (pin "2") (pinfunction "2_2") (pintype "passive"))
      (node (ref "J2") (pin "P5") (pinfunction "CLK_P5") (pintype "bidirectional"))
      (node (ref "J3") (pin "13") (pinfunction "13_13") (pintype "bidirectional"))
      (node (ref "R_SCK") (pin "1") (pinfunction "1_1") (pintype "passive"))
      (node (ref "SCK") (pin "TP") (pinfunction "TP_TP") (pintype "input"))
      (node (ref "U1") (pin "6") (pinfunction "IO6_6") (pintype "bidirectional"))
      (node (ref "U4") (pin "6") (pinfunction "CLK_6") (pintype "input"))
    )
    (net (code "46") (name "SCL") (class "Default")
      (node (ref "J4") (pin "4") (pinfunction "4_4") (pintype "passive"))
      (node (ref "R6") (pin "1") (pinfunction "1_1") (pintype "passive"))
      (node (ref "SENSOR2") (pin "4") (pinfunction "SCK_4") (pintype "input"))
      (node (ref "U1") (pin "20") (pinfunction "IO22_20") (pintype "bidirectional"))
      (node (ref "U2") (pin "7") (pinfunction "SCL_7") (pintype "input"))
      (node (ref "U3") (pin "16") (pinfunction "SCL_16") (pintype "input"))
    )
    (net (code "47") (name "SDA") (class "Default")
      (node (ref "J4") (pin "3") (pinfunction "3_3") (pintype "passive"))
      (node (ref "R7") (pin "1") (pinfunction "1_1") (pintype "passive"))
      (node (ref "SENSOR2") (pin "3") (pinfunction "SDI_3") (pintype "bidirectional"))
      (node (ref "U1") (pin "19") (pinfunction "IO21_19") (pintype "bidirectional"))
      (node (ref "U2") (pin "8") (pinfunction "SDA_8") (pintype "bidirectional"))
      (node (ref "U3") (pin "15") (pinfunction "SDA_15") (pintype "bidirectional"))
    )
    (net (code "48") (name "SRC") (class "Default")
      (node (ref "C5") (pin "2") (pinfunction "2_2") (pintype "passive"))
      (node (ref "D5") (pin "2") (pinfunction "A_2") (pintype "bidirectional"))
      (node (ref "L1") (pin "1") (pinfunction "1_1") (pintype "passive"))
      (node (ref "Q2") (pin "3") (pinfunction "D_3") (pintype "bidirectional"))
    )
    (net (code "49") (name "SS_SD") (class "Default")
      (node (ref "D_SS_SD") (pin "2") (pinfunction "2_2") (pintype "passive"))
      (node (ref "J2") (pin "P2") (pinfunction "CD/DAT3_P2") (pintype "bidirectional"))
      (node (ref "R_SS_SD") (pin "1") (pinfunction "1_1") (pintype "passive"))
      (node (ref "U1") (pin "4") (pinfunction "IO4_4") (pintype "bidirectional"))
    )
    (net (code "50") (name "TX") (class "Default")
      (node (ref "TX") (pin "TP") (pinfunction "TP_TP") (pintype "input"))
      (node (ref "U1") (pin "25") (pinfunction "TXD0/GPIO16_25") (pintype "bidirectional"))
    )
    (net (code "51") (name "USB_D+") (class "Default")
      (node (ref "D1") (pin "3") (pinfunction "I/O2_1_3") (pintype "bidirectional"))
      (node (ref "U1") (pin "14") (pinfunction "IO13_14") (pintype "bidirectional"))
    )
    (net (code "52") (name "USB_D-") (class "Default")
      (node (ref "D1") (pin "1") (pinfunction "I/O1_1_1") (pintype "bidirectional"))
      (node (ref "U1") (pin "13") (pinfunction "IO12_13") (pintype "bidirectional"))
    )
    (net (code "53") (name "VBAT") (class "Default")
      (node (ref "C2_BAT") (pin "1") (pinfunction "1_1") (pintype "passive"))
      (node (ref "MCP73831") (pin "3") (pinfunction "VBAT_3") (pintype "power_in"))
      (node (ref "Q1") (pin "3") (pinfunction "D_3") (pintype "bidirectional"))
      (node (ref "U2") (pin "2") (pinfunction "CELL_2") (pintype "power_in"))
      (node (ref "U2") (pin "3") (pinfunction "VDD_3") (pintype "power_in"))
      (node (ref "VBAT") (pin "TP") (pinfunction "TP_TP") (pintype "input"))
    )
    (net (code "54") (name "VBUS") (class "Default")
      (node (ref "C1") (pin "1") (pinfunction "1_1") (pintype "passive"))
      (node (ref "C1_BAT") (pin "1") (pinfunction "1_1") (pintype "passive"))
      (node (ref "C2") (pin "1") (pinfunction "1_1") (pintype "passive"))
      (node (ref "CHG_LED") (pin "A") (pinfunction "A_A") (pintype "passive"))
      (node (ref "D1") (pin "5") (pinfunction "VBUS_5") (pintype "bidirectional"))
      (node (ref "D2") (pin "2") (pinfunction "ANODE_2") (pintype "bidirectional"))
      (node (ref "MCP73831") (pin "4") (pinfunction "VIN_4") (pintype "power_in"))
      (node (ref "Q1") (pin "1") (pinfunction "G_1") (pintype "bidirectional"))
      (node (ref "R1") (pin "2") (pinfunction "2_2") (pintype "passive"))
      (node (ref "R1_PWRUSB") (pin "2") (pinfunction "2_2") (pintype "passive"))
      (node (ref "VBUS") (pin "TP") (pinfunction "TP_TP") (pintype "input"))
    )
    (net (code "55") (name "VRTC") (class "Default")
      (node (ref "C23") (pin "1") (pinfunction "1_1") (pintype "passive"))
      (node (ref "C24") (pin "1") (pinfunction "1_1") (pintype "passive"))
      (node (ref "R10") (pin "2") (pinfunction "2_2") (pintype "passive"))
      (node (ref "U3") (pin "14") (pinfunction "VBAT_14") (pintype "power_in"))
    )
    (net (code "56") (name "VUSB") (class "Default")
      (node (ref "J1") (pin "A4") (pinfunction "A4_A4") (pintype "bidirectional"))
      (node (ref "J1") (pin "A9") (pinfunction "A9_A9") (pintype "bidirectional"))
      (node (ref "J1") (pin "B4") (pinfunction "B4_B4") (pintype "bidirectional"))
      (node (ref "J1") (pin "B9") (pinfunction "B9_B9") (pintype "bidirectional"))
      (node (ref "R1") (pin "1") (pinfunction "1_1") (pintype "passive"))
    )
    (net (code "57") (name "unconnected-(IC1-CE-Pad3)") (class "Default")
      (node (ref "IC1") (pin "3") (pinfunction "CE_3") (pintype "bidirectional"))
    )
    (net (code "58") (name "unconnected-(IC1-NC-Pad4)") (class "Default")
      (node (ref "IC1") (pin "4") (pinfunction "NC_4") (pintype "no_connect"))
    )
    (net (code "59") (name "unconnected-(IC1-VOUT-Pad5)") (class "Default")
      (node (ref "IC1") (pin "5") (pinfunction "VOUT_5") (pintype "bidirectional"))
    )
    (net (code "60") (name "unconnected-(IC2-NC-Pad4)") (class "Default")
      (node (ref "IC2") (pin "4") (pinfunction "NC_4") (pintype "no_connect"))
    )
    (net (code "61") (name "unconnected-(J1-PadA8)") (class "Default")
      (node (ref "J1") (pin "A8") (pinfunction "A8_A8") (pintype "bidirectional"))
    )
    (net (code "62") (name "unconnected-(J1-PadB8)") (class "Default")
      (node (ref "J1") (pin "B8") (pinfunction "B8_B8") (pintype "bidirectional"))
    )
    (net (code "63") (name "unconnected-(J2-DAT1-PadP8)") (class "Default")
      (node (ref "J2") (pin "P8") (pinfunction "DAT1_P8") (pintype "bidirectional"))
    )
    (net (code "64") (name "unconnected-(J2-DAT2-PadP1)") (class "Default")
      (node (ref "J2") (pin "P1") (pinfunction "DAT2_P1") (pintype "bidirectional"))
    )
    (net (code "65") (name "unconnected-(J2-DETECTION_1-PadS1)") (class "Default")
      (node (ref "J2") (pin "S1") (pinfunction "DETECTION_1_S1") (pintype "bidirectional"))
    )
    (net (code "66") (name "unconnected-(J2-DETECTION_2-PadS2)") (class "Default")
      (node (ref "J2") (pin "S2") (pinfunction "DETECTION_2_S2") (pintype "bidirectional"))
    )
    (net (code "67") (name "unconnected-(J3-Pad1)") (class "Default")
      (node (ref "J3") (pin "1") (pinfunction "1_1") (pintype "bidirectional"))
    )
    (net (code "68") (name "unconnected-(J3-Pad6)") (class "Default")
      (node (ref "J3") (pin "6") (pinfunction "6_6") (pintype "bidirectional"))
    )
    (net (code "69") (name "unconnected-(J3-Pad7)") (class "Default")
      (node (ref "J3") (pin "7") (pinfunction "7_7") (pintype "bidirectional"))
    )
    (net (code "70") (name "unconnected-(U1-NC-Pad22)") (class "Default")
      (node (ref "U1") (pin "22") (pinfunction "NC_22") (pintype "no_connect"))
    )
    (net (code "71") (name "unconnected-(U2-~{ALERT}-Pad5)") (class "Default")
      (node (ref "U2") (pin "5") (pinfunction "~{ALERT}_5") (pintype "output"))
    )
  )
)
